# 28pins_schematic.net
KiCad netlist of a schematic drawn in Altium Designer
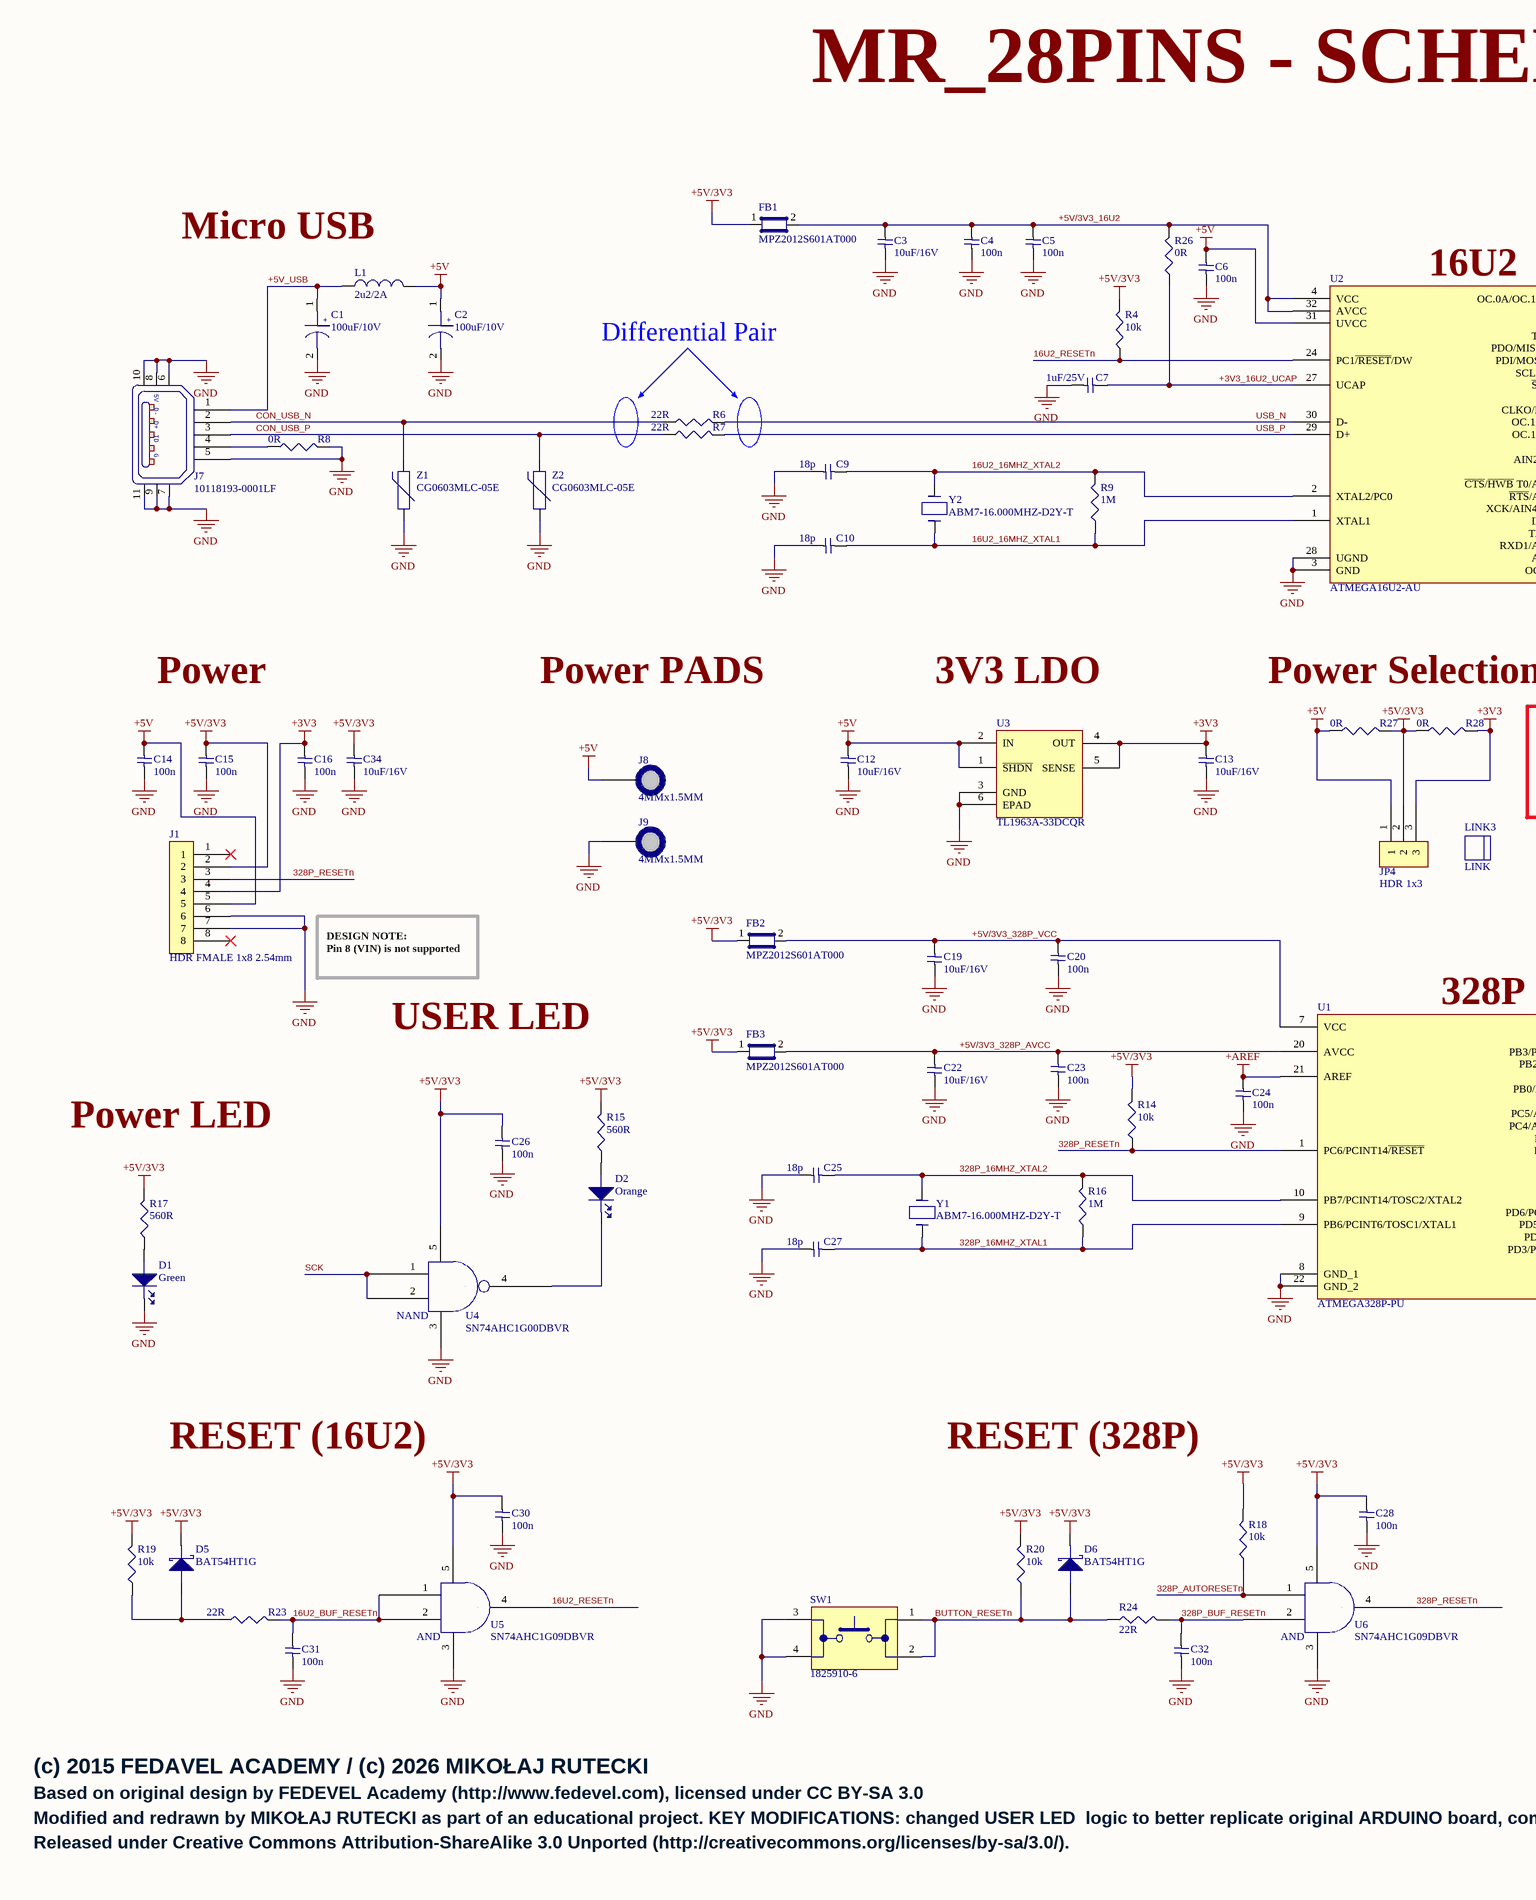
[diagram p0: 28pins_schematic.SchDoc, left]
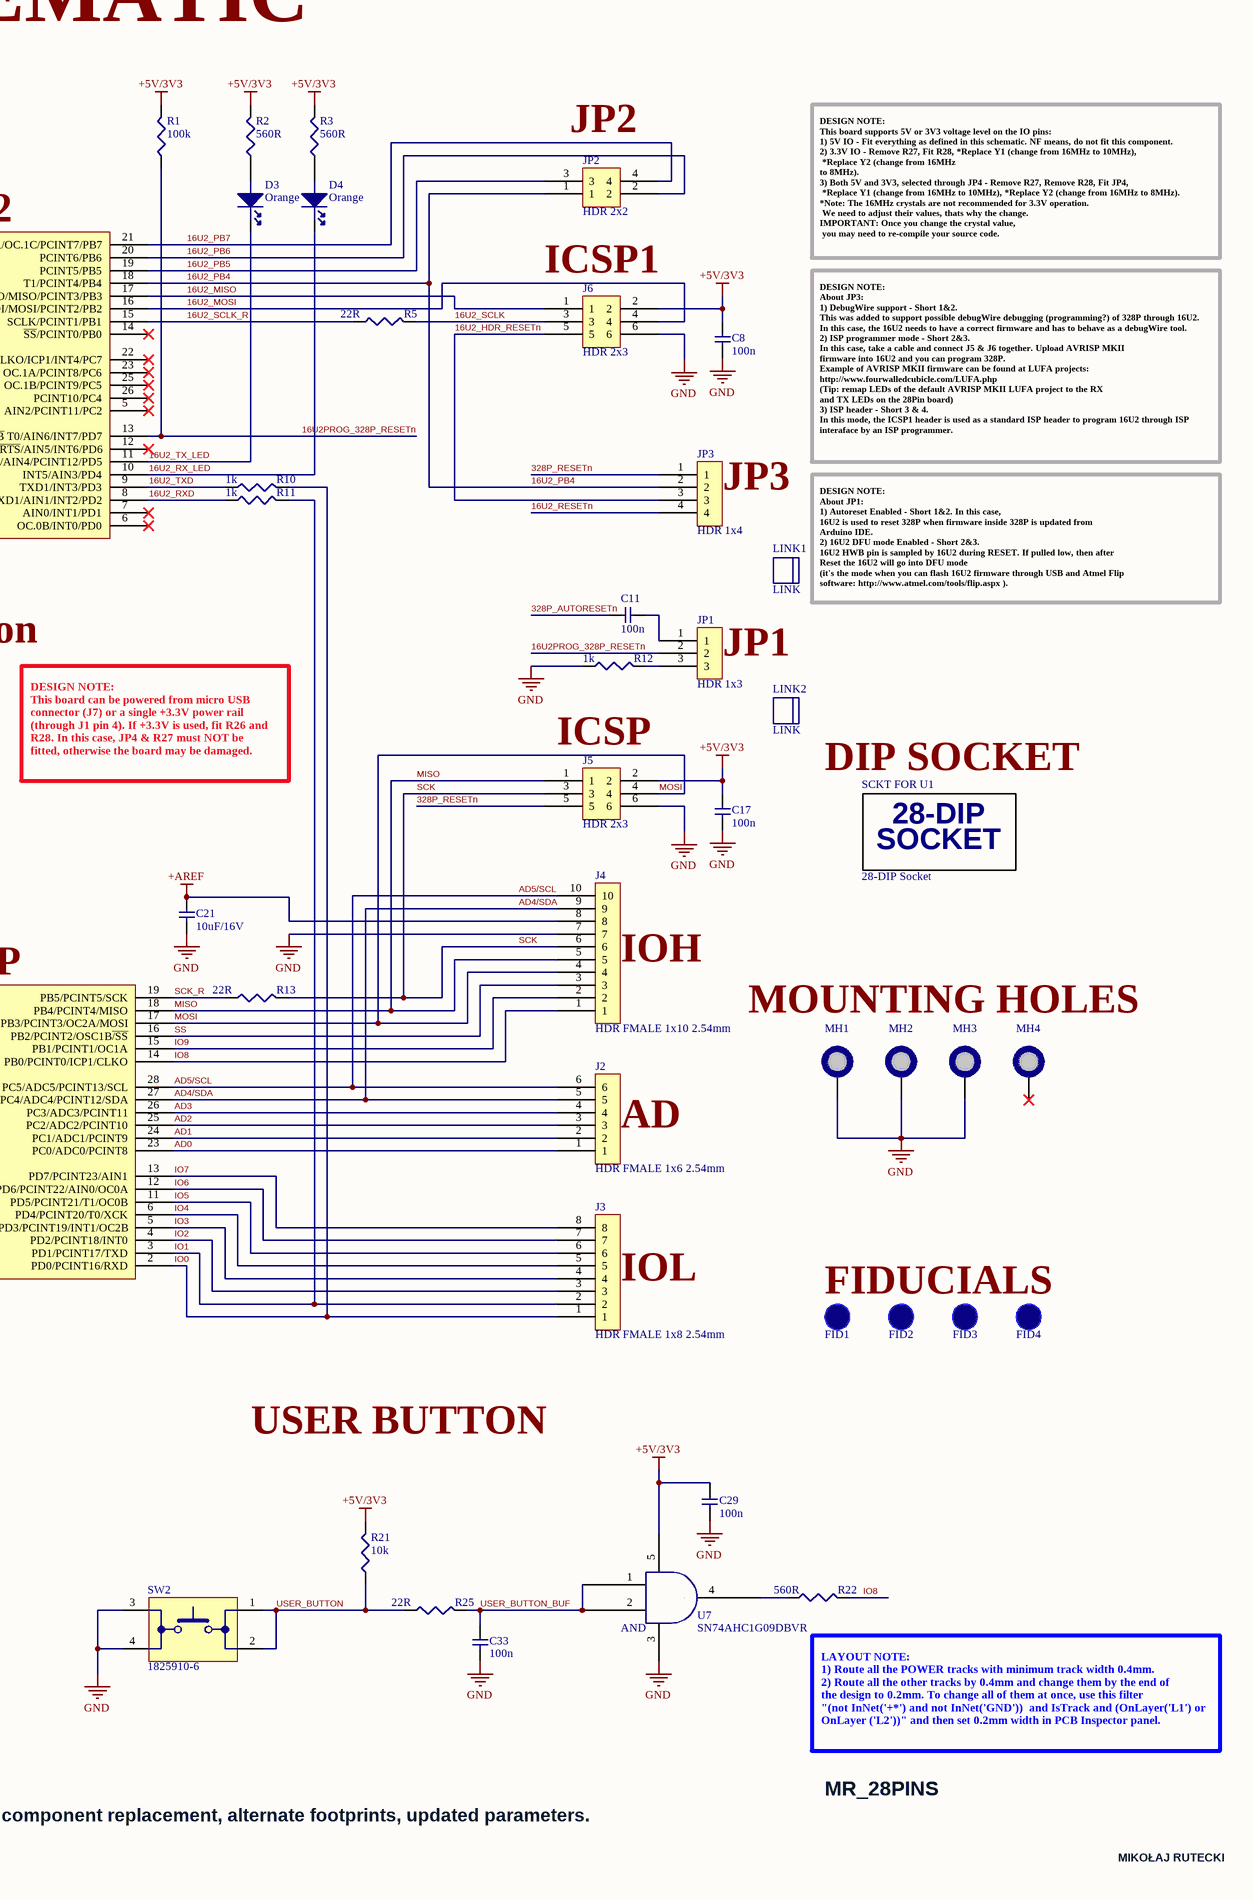
[diagram p1: 28pins_schematic.SchDoc, right]

(export (version "E")
  (design (tool "Eeschema 10.0.6"))
  (components
    (comp (ref "C1")
      (value "100uF/10V")
      (footprint "C_ALU_C_SIZE")
      (description "CAP ALUM 100UF 20% 10V SMD")
      (libsource (lib "28Pins_Project_V1I1") (part "EEE-1AA101WR"))
    )
    (comp (ref "C2")
      (value "100uF/10V")
      (footprint "C_ALU_C_SIZE")
      (description "CAP ALUM 100UF 20% 10V SMD")
      (libsource (lib "28Pins_Project_V1I1") (part "EEE-1AA101WR"))
    )
    (comp (ref "C3")
      (value "10uF/16V")
      (footprint "C0805")
      (description "CAP CER 10UF 16V X5R 0805")
      (libsource (lib "28Pins_Project_V1I1") (part "CGA4J1X5R1C106M125AC"))
    )
    (comp (ref "C4")
      (value "100n")
      (footprint "C0805")
      (description "CAP CER 0.1UF 50V X7R 0805")
      (libsource (lib "28Pins_Project_V1I1") (part "C2012X7R1H104K085AA"))
    )
    (comp (ref "C5")
      (value "100n")
      (footprint "C0805")
      (description "CAP CER 0.1UF 50V X7R 0805")
      (libsource (lib "28Pins_Project_V1I1") (part "C2012X7R1H104K085AA"))
    )
    (comp (ref "C6")
      (value "100n")
      (footprint "C0805")
      (description "CAP CER 0.1UF 50V X7R 0805")
      (libsource (lib "28Pins_Project_V1I1") (part "C2012X7R1H104K085AA"))
    )
    (comp (ref "C7")
      (value "1uF/25V")
      (footprint "C0805")
      (description "CAP CER 1UF 25V X5R 0805")
      (libsource (lib "28Pins_Project_V1I1") (part "C2012X5R1E105K125AA"))
    )
    (comp (ref "C8")
      (value "100n")
      (footprint "C0805")
      (description "CAP CER 0.1UF 50V X7R 0805")
      (libsource (lib "28Pins_Project_V1I1") (part "C2012X7R1H104K085AA"))
    )
    (comp (ref "C9")
      (value "18p")
      (footprint "C0805")
      (description "CAP CER 18PF 50V NP0 0805")
      (libsource (lib "28Pins_Project_V1I1") (part "C0805C180J5GACTU"))
    )
    (comp (ref "C10")
      (value "18p")
      (footprint "C0805")
      (description "CAP CER 18PF 50V NP0 0805")
      (libsource (lib "28Pins_Project_V1I1") (part "C0805C180J5GACTU"))
    )
    (comp (ref "C11")
      (value "100n")
      (footprint "C0805")
      (description "CAP CER 0.1UF 50V X7R 0805")
      (libsource (lib "28Pins_Project_V1I1") (part "C2012X7R1H104K085AA"))
    )
    (comp (ref "C12")
      (value "10uF/16V")
      (footprint "C0805")
      (description "CAP CER 10UF 16V X5R 0805")
      (libsource (lib "28Pins_Project_V1I1") (part "CGA4J1X5R1C106M125AC"))
    )
    (comp (ref "C13")
      (value "10uF/16V")
      (footprint "C0805")
      (description "CAP CER 10UF 16V X5R 0805")
      (libsource (lib "28Pins_Project_V1I1") (part "CGA4J1X5R1C106M125AC"))
    )
    (comp (ref "C14")
      (value "100n")
      (footprint "C0805")
      (description "CAP CER 0.1UF 50V X7R 0805")
      (libsource (lib "28Pins_Project_V1I1") (part "C2012X7R1H104K085AA"))
    )
    (comp (ref "C15")
      (value "100n")
      (footprint "C0805")
      (description "CAP CER 0.1UF 50V X7R 0805")
      (libsource (lib "28Pins_Project_V1I1") (part "C2012X7R1H104K085AA"))
    )
    (comp (ref "C16")
      (value "100n")
      (footprint "C0805")
      (description "CAP CER 0.1UF 50V X7R 0805")
      (libsource (lib "28Pins_Project_V1I1") (part "C2012X7R1H104K085AA"))
    )
    (comp (ref "C17")
      (value "100n")
      (footprint "C0805")
      (description "CAP CER 0.1UF 50V X7R 0805")
      (libsource (lib "28Pins_Project_V1I1") (part "C2012X7R1H104K085AA"))
    )
    (comp (ref "C19")
      (value "10uF/16V")
      (footprint "C0805")
      (description "CAP CER 10UF 16V X5R 0805")
      (libsource (lib "28Pins_Project_V1I1") (part "CGA4J1X5R1C106M125AC"))
    )
    (comp (ref "C20")
      (value "100n")
      (footprint "C0805")
      (description "CAP CER 0.1UF 50V X7R 0805")
      (libsource (lib "28Pins_Project_V1I1") (part "C2012X7R1H104K085AA"))
    )
    (comp (ref "C21")
      (value "10uF/16V")
      (footprint "C0805")
      (description "CAP CER 10UF 16V X5R 0805")
      (libsource (lib "28Pins_Project_V1I1") (part "CGA4J1X5R1C106M125AC"))
    )
    (comp (ref "C22")
      (value "10uF/16V")
      (footprint "C0805")
      (description "CAP CER 10UF 16V X5R 0805")
      (libsource (lib "28Pins_Project_V1I1") (part "CGA4J1X5R1C106M125AC"))
    )
    (comp (ref "C23")
      (value "100n")
      (footprint "C0805")
      (description "CAP CER 0.1UF 50V X7R 0805")
      (libsource (lib "28Pins_Project_V1I1") (part "C2012X7R1H104K085AA"))
    )
    (comp (ref "C24")
      (value "100n")
      (footprint "C0805")
      (description "CAP CER 0.1UF 50V X7R 0805")
      (libsource (lib "28Pins_Project_V1I1") (part "C2012X7R1H104K085AA"))
    )
    (comp (ref "C25")
      (value "18p")
      (footprint "C0805")
      (description "CAP CER 18PF 50V NP0 0805")
      (libsource (lib "28Pins_Project_V1I1") (part "C0805C180J5GACTU"))
    )
    (comp (ref "C26")
      (value "100n")
      (footprint "C0805")
      (description "CAP CER 0.1UF 50V X7R 0805")
      (libsource (lib "28Pins_Project_V1I1") (part "C2012X7R1H104K085AA"))
    )
    (comp (ref "C27")
      (value "18p")
      (footprint "C0805")
      (description "CAP CER 18PF 50V NP0 0805")
      (libsource (lib "28Pins_Project_V1I1") (part "C0805C180J5GACTU"))
    )
    (comp (ref "C28")
      (value "100n")
      (footprint "C0805")
      (description "CAP CER 0.1UF 50V X7R 0805")
      (libsource (lib "28Pins_Project_V1I1") (part "C2012X7R1H104K085AA"))
    )
    (comp (ref "C29")
      (value "100n")
      (footprint "C0805")
      (description "CAP CER 0.1UF 50V X7R 0805")
      (libsource (lib "28Pins_Project_V1I1") (part "C2012X7R1H104K085AA"))
    )
    (comp (ref "C30")
      (value "100n")
      (footprint "C0805")
      (description "CAP CER 0.1UF 50V X7R 0805")
      (libsource (lib "28Pins_Project_V1I1") (part "C2012X7R1H104K085AA"))
    )
    (comp (ref "C31")
      (value "100n")
      (footprint "C0805")
      (description "CAP CER 0.1UF 50V X7R 0805")
      (libsource (lib "28Pins_Project_V1I1") (part "C2012X7R1H104K085AA"))
    )
    (comp (ref "C32")
      (value "100n")
      (footprint "C0805")
      (description "CAP CER 0.1UF 50V X7R 0805")
      (libsource (lib "28Pins_Project_V1I1") (part "C2012X7R1H104K085AA"))
    )
    (comp (ref "C33")
      (value "100n")
      (footprint "C0805")
      (description "CAP CER 0.1UF 50V X7R 0805")
      (libsource (lib "28Pins_Project_V1I1") (part "C2012X7R1H104K085AA"))
    )
    (comp (ref "C34")
      (value "10uF/16V")
      (footprint "C0805")
      (description "CAP CER 10UF 16V X5R 0805")
      (libsource (lib "28Pins_Project_V1I1") (part "CGA4J1X5R1C106M125AC"))
    )
    (comp (ref "D1")
      (value "Green")
      (footprint "LED_0603")
      (description "LED GREEN DIFFUSED 0603 SMD")
      (libsource (lib "28Pins_Project_V1I1") (part "LG L29K-G2J1-24-0-2-R18-Z"))
    )
    (comp (ref "D2")
      (value "Orange")
      (footprint "LED_0603")
      (description "LED ORANGE DIFFUSED 0603 SMD")
      (libsource (lib "28Pins_Project_V1I1") (part "LO L29K-H2K1-24-0-2-R18-Z"))
    )
    (comp (ref "D3")
      (value "Orange")
      (footprint "LED_0603")
      (description "LED ORANGE DIFFUSED 0603 SMD")
      (libsource (lib "28Pins_Project_V1I1") (part "LO L29K-H2K1-24-0-2-R18-Z"))
    )
    (comp (ref "D4")
      (value "Orange")
      (footprint "LED_0603")
      (description "LED ORANGE DIFFUSED 0603 SMD")
      (libsource (lib "28Pins_Project_V1I1") (part "LO L29K-H2K1-24-0-2-R18-Z"))
    )
    (comp (ref "D5")
      (value "BAT54HT1G")
      (footprint "SOD323")
      (description "DIODE SCHOTTKY 30V 200MA SOD323")
      (libsource (lib "28Pins_Project_V1I1") (part "BAT54HT1GOSCT-ND"))
    )
    (comp (ref "D6")
      (value "BAT54HT1G")
      (footprint "SOD323")
      (description "DIODE SCHOTTKY 30V 200MA SOD323")
      (libsource (lib "28Pins_Project_V1I1") (part "BAT54HT1GOSCT-ND"))
    )
    (comp (ref "FB1")
      (value "MPZ2012S601AT000")
      (footprint "C0805")
      (description "FERRITE CHIP BEAD 600 OHM SMD")
      (libsource (lib "28Pins_Project_V1I1") (part "MPZ2012S601AT000"))
    )
    (comp (ref "FB2")
      (value "MPZ2012S601AT000")
      (footprint "C0805")
      (description "FERRITE CHIP BEAD 600 OHM SMD")
      (libsource (lib "28Pins_Project_V1I1") (part "MPZ2012S601AT000"))
    )
    (comp (ref "FB3")
      (value "MPZ2012S601AT000")
      (footprint "C0805")
      (description "FERRITE CHIP BEAD 600 OHM SMD")
      (libsource (lib "28Pins_Project_V1I1") (part "MPZ2012S601AT000"))
    )
    (comp (ref "FID1")
      (value "FID_1MM")
      (footprint "FID_40x120D")
      (description "Fiducial 40mil Diameter, 120mil Mask")
      (libsource (lib "28Pins_Project_V1I1") (part "FID_1MM"))
    )
    (comp (ref "FID2")
      (value "FID_1MM")
      (footprint "FID_40x120D")
      (description "Fiducial 40mil Diameter, 120mil Mask")
      (libsource (lib "28Pins_Project_V1I1") (part "FID_1MM"))
    )
    (comp (ref "FID3")
      (value "FID_1MM")
      (footprint "FID_40x120D")
      (description "Fiducial 40mil Diameter, 120mil Mask")
      (libsource (lib "28Pins_Project_V1I1") (part "FID_1MM"))
    )
    (comp (ref "FID4")
      (value "FID_1MM")
      (footprint "FID_40x120D")
      (description "Fiducial 40mil Diameter, 120mil Mask")
      (libsource (lib "28Pins_Project_V1I1") (part "FID_1MM"))
    )
    (comp (ref "J1")
      (value "HDR FMALE 1x8 2.54mm")
      (footprint "HDR_Female_1x8_2.54mm - duplicate")
      (description "8-WAY SIL VERT SOCKET L/FREE")
      (libsource (lib "") (part "M20-7820842_1"))
    )
    (comp (ref "J2")
      (value "HDR FMALE 1x6 2.54mm")
      (footprint "HDR_Female_1x6_2.54mm")
      (description "6-WAY SIL VERT SOCKET L/FREE")
      (libsource (lib "28Pins_Project_V1I1") (part "M20-7820646"))
    )
    (comp (ref "J3")
      (value "HDR FMALE 1x8 2.54mm")
      (footprint "HDR_Female_1x8_2.54mm - duplicate")
      (description "8-WAY SIL VERT SOCKET L/FREE")
      (libsource (lib "28Pins_Project_V1I1") (part "M20-7820842"))
    )
    (comp (ref "J4")
      (value "HDR FMALE 1x10 2.54mm")
      (footprint "HDR_Female_1x10_2.54mm")
      (description "10-WAY SIL VERT SOCKET L/FREE")
      (libsource (lib "28Pins_Project_V1I1") (part "M20-7821046"))
    )
    (comp (ref "J5")
      (value "HDR 2x3")
      (footprint "HDR_2x3_2.54MM")
      (description "CONN HEADER VERT 6POS 2.54MM")
      (libsource (lib "28Pins_Project_V1I1") (part "87227-3"))
    )
    (comp (ref "J6")
      (value "HDR 2x3")
      (footprint "HDR_2x3_2.54MM")
      (description "CONN HEADER VERT 6POS 2.54MM")
      (libsource (lib "28Pins_Project_V1I1") (part "87227-3"))
    )
    (comp (ref "J7")
      (value "10118193-0001LF")
      (footprint "10118193")
      (description "CONN RCPT USB2.0 MICRO B SMD R/A")
      (libsource (lib "28Pins_Project_V1I1") (part "10118193-0001LF"))
    )
    (comp (ref "J8")
      (value "4MMx1.5MM")
      (footprint "PAD_WITH_HOLE_4MMx1.5MM")
      (description "Pad with a hole 4mmx1.5mm")
      (libsource (lib "28Pins_Project_V1I1") (part "PAD_WITH_HOLE_4MMx1.5MM"))
    )
    (comp (ref "J9")
      (value "4MMx1.5MM")
      (footprint "PAD_WITH_HOLE_4MMx1.5MM")
      (description "Pad with a hole 4mmx1.5mm")
      (libsource (lib "28Pins_Project_V1I1") (part "PAD_WITH_HOLE_4MMx1.5MM"))
    )
    (comp (ref "JP1")
      (value "HDR 1x3")
      (footprint "HDR_1x3_2.54mm")
      (description "CONN HEADER VERT 3POS 2.54MM")
      (libsource (lib "28Pins_Project_V1I1") (part "68000-103HLF"))
    )
    (comp (ref "JP2")
      (value "HDR 2x2")
      (footprint "HDR_2x2_2.54mm")
      (description "CONN HEADER VERT 4POS 2.54MM")
      (libsource (lib "28Pins_Project_V1I1") (part "5-146256-2"))
    )
    (comp (ref "JP3")
      (value "HDR 1x4")
      (footprint "HDR_1x4_2.54mm")
      (description "CONN HEADER VERT 4POS 2.54MM")
      (libsource (lib "28Pins_Project_V1I1") (part "68001-204HLF"))
    )
    (comp (ref "JP4")
      (value "HDR 1x3")
      (footprint "HDR_1x3_2.54mm")
      (description "CONN HEADER VERT 3POS 2.54MM")
      (libsource (lib "") (part "68000-103HLF_1"))
    )
    (comp (ref "L1")
      (value "2u2/2A")
      (footprint "C1210_IND")
      (description "FIXED IND 2.2UH 2A 80 MOHM SMD")
      (libsource (lib "28Pins_Project_V1I1") (part "L1210R2R2MDWIT"))
    )
    (comp (ref "LINK1")
      (value "LINK")
      (description "CONN JUMPER SHORTING .100\" GOLD")
      (libsource (lib "28Pins_Project_V1I1") (part "QPC02SXGN-RC"))
    )
    (comp (ref "LINK2")
      (value "LINK")
      (description "CONN JUMPER SHORTING .100\" GOLD")
      (libsource (lib "28Pins_Project_V1I1") (part "QPC02SXGN-RC"))
    )
    (comp (ref "LINK3")
      (value "LINK")
      (description "CONN JUMPER SHORTING .100\" GOLD")
      (libsource (lib "28Pins_Project_V1I1") (part "QPC02SXGN-RC"))
    )
    (comp (ref "MH1")
      (value "MH_7.4MMC_3.2MMD")
      (footprint "MH_7.4MMD_3.2MMD")
      (description "Mounting Hole 7.4mm Diameter, 3.2mm Drill")
      (libsource (lib "28Pins_Project_V1I1") (part "MH_7.4MMC_3.2MMD"))
    )
    (comp (ref "MH2")
      (value "MH_7.4MMC_3.2MMD")
      (footprint "MH_7.4MMD_3.2MMD")
      (description "Mounting Hole 7.4mm Diameter, 3.2mm Drill")
      (libsource (lib "28Pins_Project_V1I1") (part "MH_7.4MMC_3.2MMD"))
    )
    (comp (ref "MH3")
      (value "MH_7.4MMC_3.2MMD")
      (footprint "MH_7.4MMD_3.2MMD")
      (description "Mounting Hole 7.4mm Diameter, 3.2mm Drill")
      (libsource (lib "28Pins_Project_V1I1") (part "MH_7.4MMC_3.2MMD"))
    )
    (comp (ref "MH4")
      (value "MH_7.4MMNC_3.2MMD")
      (footprint "MH_7.4MMD_3.2MMD_NON_COPPER_NPTH")
      (description "Hole 7.4mm Diameter (NON COPPER), 3.2mm Drill NPTH")
      (libsource (lib "28Pins_Project_V1I1") (part "MH_7.4MMNC_3.2MMD"))
    )
    (comp (ref "R1")
      (value "100k")
      (footprint "R0805")
      (description "RES 100K OHM 5% 1/8W 0805")
      (libsource (lib "28Pins_Project_V1I1") (part "RC0805JR-07100KL"))
    )
    (comp (ref "R2")
      (value "560R")
      (footprint "R0805")
      (description "RES 560 OHM 1% 1/8W 0805")
      (libsource (lib "28Pins_Project_V1I1") (part "RC0805FR-07560RL"))
    )
    (comp (ref "R3")
      (value "560R")
      (footprint "R0805")
      (description "RES 560 OHM 1% 1/8W 0805")
      (libsource (lib "28Pins_Project_V1I1") (part "RC0805FR-07560RL"))
    )
    (comp (ref "R4")
      (value "10k")
      (footprint "R0805")
      (description "RES 10K OHM 1% 1/8W 0805")
      (libsource (lib "28Pins_Project_V1I1") (part "RC0805FR-0710KL"))
    )
    (comp (ref "R5")
      (value "22R")
      (footprint "R0805")
      (description "RES SMD 22 OHM 1% 1/8W 0805")
      (libsource (lib "28Pins_Project_V1I1") (part "RT0805FRE0722RL"))
    )
    (comp (ref "R6")
      (value "22R")
      (footprint "R0805")
      (description "RES SMD 22 OHM 1% 1/8W 0805")
      (libsource (lib "28Pins_Project_V1I1") (part "RT0805FRE0722RL"))
    )
    (comp (ref "R7")
      (value "22R")
      (footprint "R0805")
      (description "RES SMD 22 OHM 1% 1/8W 0805")
      (libsource (lib "28Pins_Project_V1I1") (part "RT0805FRE0722RL"))
    )
    (comp (ref "R8")
      (value "0R")
      (footprint "R0805")
      (description "RES 0 OHM JUMPER 1/8W 0805")
      (libsource (lib "28Pins_Project_V1I1") (part "RC0805JR-070RL"))
    )
    (comp (ref "R9")
      (value "1M")
      (footprint "R0805")
      (description "RES SMD 1M OHM 1% 1/8W 0805")
      (libsource (lib "28Pins_Project_V1I1") (part "RC0805FR-071ML"))
    )
    (comp (ref "R10")
      (value "1k")
      (footprint "R0805")
      (description "RES 1K OHM 1% 1/8W 0805")
      (libsource (lib "28Pins_Project_V1I1") (part "RC0805FR-071KL"))
    )
    (comp (ref "R11")
      (value "1k")
      (footprint "R0805")
      (description "RES 1K OHM 1% 1/8W 0805")
      (libsource (lib "28Pins_Project_V1I1") (part "RC0805FR-071KL"))
    )
    (comp (ref "R12")
      (value "1k")
      (footprint "R0805")
      (description "RES 1K OHM 1% 1/8W 0805")
      (libsource (lib "28Pins_Project_V1I1") (part "RC0805FR-071KL"))
    )
    (comp (ref "R13")
      (value "22R")
      (footprint "R0805")
      (description "RES SMD 22 OHM 1% 1/8W 0805")
      (libsource (lib "28Pins_Project_V1I1") (part "RT0805FRE0722RL"))
    )
    (comp (ref "R14")
      (value "10k")
      (footprint "R0805")
      (description "RES 10K OHM 1% 1/8W 0805")
      (libsource (lib "28Pins_Project_V1I1") (part "RC0805FR-0710KL"))
    )
    (comp (ref "R15")
      (value "560R")
      (footprint "R0805")
      (description "RES 560 OHM 1% 1/8W 0805")
      (libsource (lib "28Pins_Project_V1I1") (part "RC0805FR-07560RL"))
    )
    (comp (ref "R16")
      (value "1M")
      (footprint "R0805")
      (description "RES SMD 1M OHM 1% 1/8W 0805")
      (libsource (lib "28Pins_Project_V1I1") (part "RC0805FR-071ML"))
    )
    (comp (ref "R17")
      (value "560R")
      (footprint "R0805")
      (description "RES 560 OHM 1% 1/8W 0805")
      (libsource (lib "28Pins_Project_V1I1") (part "RC0805FR-07560RL"))
    )
    (comp (ref "R18")
      (value "10k")
      (footprint "R0805")
      (description "RES 10K OHM 1% 1/8W 0805")
      (libsource (lib "28Pins_Project_V1I1") (part "RC0805FR-0710KL"))
    )
    (comp (ref "R19")
      (value "10k")
      (footprint "R0805")
      (description "RES 10K OHM 1% 1/8W 0805")
      (libsource (lib "28Pins_Project_V1I1") (part "RC0805FR-0710KL"))
    )
    (comp (ref "R20")
      (value "10k")
      (footprint "R0805")
      (description "RES 10K OHM 1% 1/8W 0805")
      (libsource (lib "28Pins_Project_V1I1") (part "RC0805FR-0710KL"))
    )
    (comp (ref "R21")
      (value "10k")
      (footprint "R0805")
      (description "RES 10K OHM 1% 1/8W 0805")
      (libsource (lib "28Pins_Project_V1I1") (part "RC0805FR-0710KL"))
    )
    (comp (ref "R22")
      (value "560R")
      (footprint "R0805")
      (description "RES 560 OHM 1% 1/8W 0805")
      (libsource (lib "28Pins_Project_V1I1") (part "RC0805FR-07560RL"))
    )
    (comp (ref "R23")
      (value "22R")
      (footprint "R0805")
      (description "RES SMD 22 OHM 1% 1/8W 0805")
      (libsource (lib "28Pins_Project_V1I1") (part "RT0805FRE0722RL"))
    )
    (comp (ref "R24")
      (value "22R")
      (footprint "R0805")
      (description "RES SMD 22 OHM 1% 1/8W 0805")
      (libsource (lib "28Pins_Project_V1I1") (part "RT0805FRE0722RL"))
    )
    (comp (ref "R25")
      (value "22R")
      (footprint "R0805")
      (description "RES SMD 22 OHM 1% 1/8W 0805")
      (libsource (lib "28Pins_Project_V1I1") (part "RT0805FRE0722RL"))
    )
    (comp (ref "R26")
      (value "0R")
      (footprint "R0805")
      (description "RES 0 OHM JUMPER 1/8W 0805")
      (libsource (lib "28Pins_Project_V1I1") (part "RC0805JR-070RL"))
    )
    (comp (ref "R27")
      (value "0R")
      (footprint "R0805")
      (description "RES 0 OHM JUMPER 1/8W 0805")
      (libsource (lib "28Pins_Project_V1I1") (part "RC0805JR-070RL"))
    )
    (comp (ref "R28")
      (value "0R")
      (footprint "R0805")
      (description "RES 0 OHM JUMPER 1/8W 0805")
      (libsource (lib "28Pins_Project_V1I1") (part "RC0805JR-070RL"))
    )
    (comp (ref "SCKT FOR U1")
      (value "28-DIP Socket")
      (footprint "28-DIP_7.62mm_SOCKET")
      (description "CONN IC DIP SOCKET 28POS TIN")
      (libsource (lib "28Pins_Project_V1I1") (part "4828-3004-CP"))
    )
    (comp (ref "SW1")
      (value "1825910-6")
      (footprint "1825910-6")
      (description "SWITCH TACTILE SPST-NO 0.05A 24V")
      (libsource (lib "28Pins_Project_V1I1") (part "1825910-6"))
    )
    (comp (ref "SW2")
      (value "1825910-6")
      (footprint "1825910-6")
      (description "SWITCH TACTILE SPST-NO 0.05A 24V")
      (libsource (lib "28Pins_Project_V1I1") (part "1825910-6"))
    )
    (comp (ref "U1")
      (value "ATMEGA328P-PU")
      (footprint "28_DIP_7.62mm")
      (description "IC MCU 8BIT 32KB FLASH 28DIP")
      (libsource (lib "28Pins_Project_V1I1") (part "ATMEGA328P-PU"))
    )
    (comp (ref "U2")
      (value "ATMEGA16U2-AU")
      (footprint "TQFP32")
      (description "IC MCU 8BIT 16KB FLASH 32TQFP")
      (libsource (lib "28Pins_Project_V1I1") (part "ATMEGA16U2-AU"))
    )
    (comp (ref "U3")
      (value "TL1963A-33DCQR")
      (footprint "DCQ(R-PDSO-G6)")
      (description "IC REG LIN 3.3V 1.5A SOT-223-6")
      (libsource (lib "28Pins_Project_V1I1") (part "TL1963A-33DCQR"))
    )
    (comp (ref "U4")
      (value "SN74AHC1G00DBVR")
      (footprint "DBV_DOT_23_5")
      (description "IC GATE NAND 1CH 2-INP SOT23-5")
      (libsource (lib "28Pins_Project_V1I1") (part "SN74AHC1G00DBVR"))
    )
    (comp (ref "U5")
      (value "SN74AHC1G09DBVR")
      (footprint "DBV_DOT_23_5")
      (description "IC GATE AND 1CH 2-INP SOT23-5")
      (libsource (lib "28Pins_Project_V1I1") (part "SN74AHC1G09DBVR"))
    )
    (comp (ref "U6")
      (value "SN74AHC1G09DBVR")
      (footprint "DBV_DOT_23_5")
      (description "IC GATE AND 1CH 2-INP SOT23-5")
      (libsource (lib "28Pins_Project_V1I1") (part "SN74AHC1G09DBVR"))
    )
    (comp (ref "U7")
      (value "SN74AHC1G09DBVR")
      (footprint "DBV_DOT_23_5")
      (description "IC GATE AND 1CH 2-INP SOT23-5")
      (libsource (lib "28Pins_Project_V1I1") (part "SN74AHC1G09DBVR"))
    )
    (comp (ref "Y1")
      (value "ABM7-16.000MHZ-D2Y-T")
      (footprint "ABM7_v1_1_BIG")
      (description "CRYSTAL 16.0000MHZ 18PF SMD")
      (libsource (lib "28Pins_Project_V1I1") (part "ABM7-16.000MHZ-D2Y-T"))
    )
    (comp (ref "Y2")
      (value "ABM7-16.000MHZ-D2Y-T")
      (footprint "ABM7_v1_1_BIG")
      (description "CRYSTAL 16.0000MHZ 18PF SMD")
      (libsource (lib "28Pins_Project_V1I1") (part "ABM7-16.000MHZ-D2Y-T"))
    )
    (comp (ref "Z1")
      (value "CG0603MLC-05E")
      (footprint "R0603")
      (description "VARISTOR 0603")
      (libsource (lib "28Pins_Project_V1I1") (part "CG0603MLC-05E"))
    )
    (comp (ref "Z2")
      (value "CG0603MLC-05E")
      (footprint "R0603")
      (description "VARISTOR 0603")
      (libsource (lib "28Pins_Project_V1I1") (part "CG0603MLC-05E"))
    )
  )
  (nets
    (net (code "1") (name "+3V3") (class "Default")
      (node (ref "C13") (pin "2") (pinfunction "2_2") (pintype "passive"))
      (node (ref "C16") (pin "2") (pinfunction "2_2") (pintype "passive"))
      (node (ref "J1") (pin "4") (pinfunction "4_4") (pintype "passive"))
      (node (ref "JP4") (pin "3") (pinfunction "3_3") (pintype "passive"))
      (node (ref "R28") (pin "2") (pinfunction "2_2") (pintype "passive"))
      (node (ref "U3") (pin "4") (pinfunction "OUT_4") (pintype "passive"))
      (node (ref "U3") (pin "5") (pinfunction "SENSE_5") (pintype "passive"))
    )
    (net (code "2") (name "+5V") (class "Default")
      (node (ref "C12") (pin "2") (pinfunction "2_2") (pintype "passive"))
      (node (ref "C14") (pin "2") (pinfunction "2_2") (pintype "passive"))
      (node (ref "C2") (pin "1") (pinfunction "1_1") (pintype "passive"))
      (node (ref "C6") (pin "2") (pinfunction "2_2") (pintype "passive"))
      (node (ref "J1") (pin "5") (pinfunction "5_5") (pintype "passive"))
      (node (ref "J8") (pin "1") (pinfunction "1_1") (pintype "passive"))
      (node (ref "JP4") (pin "1") (pinfunction "1_1") (pintype "passive"))
      (node (ref "L1") (pin "2") (pinfunction "2_2") (pintype "passive"))
      (node (ref "R27") (pin "1") (pinfunction "1_1") (pintype "passive"))
      (node (ref "U2") (pin "31") (pinfunction "UVCC_31") (pintype "passive"))
      (node (ref "U3") (pin "1") (pinfunction "~{SHDN}_1") (pintype "passive"))
      (node (ref "U3") (pin "2") (pinfunction "IN_2") (pintype "passive"))
    )
    (net (code "3") (name "+5V{slash}3V3") (class "Default")
      (node (ref "C15") (pin "2") (pinfunction "2_2") (pintype "passive"))
      (node (ref "C17") (pin "2") (pinfunction "2_2") (pintype "passive"))
      (node (ref "C26") (pin "2") (pinfunction "2_2") (pintype "passive"))
      (node (ref "C28") (pin "2") (pinfunction "2_2") (pintype "passive"))
      (node (ref "C29") (pin "2") (pinfunction "2_2") (pintype "passive"))
      (node (ref "C30") (pin "2") (pinfunction "2_2") (pintype "passive"))
      (node (ref "C34") (pin "2") (pinfunction "2_2") (pintype "passive"))
      (node (ref "C8") (pin "2") (pinfunction "2_2") (pintype "passive"))
      (node (ref "D5") (pin "1") (pinfunction "Cathode_1") (pintype "passive"))
      (node (ref "D6") (pin "1") (pinfunction "Cathode_1") (pintype "passive"))
      (node (ref "FB1") (pin "1") (pinfunction "1_1") (pintype "passive"))
      (node (ref "FB2") (pin "1") (pinfunction "1_1") (pintype "passive"))
      (node (ref "FB3") (pin "1") (pinfunction "1_1") (pintype "passive"))
      (node (ref "J1") (pin "2") (pinfunction "2_2") (pintype "passive"))
      (node (ref "J5") (pin "2") (pinfunction "2_2") (pintype "passive"))
      (node (ref "J6") (pin "2") (pinfunction "2_2") (pintype "passive"))
      (node (ref "JP4") (pin "2") (pinfunction "2_2") (pintype "passive"))
      (node (ref "R1") (pin "2") (pinfunction "2_2") (pintype "passive"))
      (node (ref "R14") (pin "2") (pinfunction "2_2") (pintype "passive"))
      (node (ref "R15") (pin "2") (pinfunction "2_2") (pintype "passive"))
      (node (ref "R17") (pin "2") (pinfunction "2_2") (pintype "passive"))
      (node (ref "R18") (pin "2") (pinfunction "2_2") (pintype "passive"))
      (node (ref "R19") (pin "2") (pinfunction "2_2") (pintype "passive"))
      (node (ref "R2") (pin "2") (pinfunction "2_2") (pintype "passive"))
      (node (ref "R20") (pin "2") (pinfunction "2_2") (pintype "passive"))
      (node (ref "R21") (pin "2") (pinfunction "2_2") (pintype "passive"))
      (node (ref "R27") (pin "2") (pinfunction "2_2") (pintype "passive"))
      (node (ref "R28") (pin "1") (pinfunction "1_1") (pintype "passive"))
      (node (ref "R3") (pin "2") (pinfunction "2_2") (pintype "passive"))
      (node (ref "R4") (pin "2") (pinfunction "2_2") (pintype "passive"))
      (node (ref "U4") (pin "5") (pinfunction "5_5") (pintype "passive"))
      (node (ref "U5") (pin "5") (pinfunction "5_5") (pintype "passive"))
      (node (ref "U6") (pin "5") (pinfunction "5_5") (pintype "passive"))
      (node (ref "U7") (pin "5") (pinfunction "5_5") (pintype "passive"))
    )
    (net (code "4") (name "+AREF") (class "Default")
      (node (ref "C21") (pin "2") (pinfunction "2_2") (pintype "passive"))
      (node (ref "C24") (pin "2") (pinfunction "2_2") (pintype "passive"))
      (node (ref "J4") (pin "8") (pinfunction "8_8") (pintype "passive"))
      (node (ref "U1") (pin "21") (pinfunction "AREF_21") (pintype "passive"))
    )
    (net (code "5") (name "/+3V3_16U2_UCAP") (class "Default")
      (node (ref "C7") (pin "2") (pinfunction "2_2") (pintype "passive"))
      (node (ref "R26") (pin "1") (pinfunction "1_1") (pintype "passive"))
      (node (ref "U2") (pin "27") (pinfunction "UCAP_27") (pintype "passive"))
    )
    (net (code "6") (name "/+5V_USB") (class "Default")
      (node (ref "C1") (pin "1") (pinfunction "1_1") (pintype "passive"))
      (node (ref "J7") (pin "1") (pinfunction "1_1") (pintype "passive"))
      (node (ref "L1") (pin "1") (pinfunction "1_1") (pintype "passive"))
    )
    (net (code "7") (name "/+5V{slash}3V3_16U2") (class "Default")
      (node (ref "C3") (pin "2") (pinfunction "2_2") (pintype "passive"))
      (node (ref "C4") (pin "2") (pinfunction "2_2") (pintype "passive"))
      (node (ref "C5") (pin "2") (pinfunction "2_2") (pintype "passive"))
      (node (ref "FB1") (pin "2") (pinfunction "2_2") (pintype "passive"))
      (node (ref "R26") (pin "2") (pinfunction "2_2") (pintype "passive"))
      (node (ref "U2") (pin "32") (pinfunction "AVCC_32") (pintype "passive"))
      (node (ref "U2") (pin "4") (pinfunction "VCC_4") (pintype "passive"))
    )
    (net (code "8") (name "/+5V{slash}3V3_328P_AVCC") (class "Default")
      (node (ref "C22") (pin "1") (pinfunction "1_1") (pintype "passive"))
      (node (ref "C23") (pin "2") (pinfunction "2_2") (pintype "passive"))
      (node (ref "FB3") (pin "2") (pinfunction "2_2") (pintype "passive"))
      (node (ref "U1") (pin "20") (pinfunction "AVCC_20") (pintype "passive"))
    )
    (net (code "9") (name "/+5V{slash}3V3_328P_VCC") (class "Default")
      (node (ref "C19") (pin "1") (pinfunction "1_1") (pintype "passive"))
      (node (ref "C20") (pin "2") (pinfunction "2_2") (pintype "passive"))
      (node (ref "FB2") (pin "2") (pinfunction "2_2") (pintype "passive"))
      (node (ref "U1") (pin "7") (pinfunction "VCC_7") (pintype "passive"))
    )
    (net (code "10") (name "/16U2PROG_328P_RESETn") (class "Default")
      (node (ref "JP1") (pin "2") (pinfunction "2_2") (pintype "passive"))
      (node (ref "R1") (pin "1") (pinfunction "1_1") (pintype "passive"))
      (node (ref "U2") (pin "13") (pinfunction "~{CTS}/~{HWB}_T0/AIN6/INT7/PD7_13") (pintype "passive"))
    )
    (net (code "11") (name "/16U2_16MHZ_XTAL1") (class "Default")
      (node (ref "C10") (pin "1") (pinfunction "1_1") (pintype "passive"))
      (node (ref "R9") (pin "1") (pinfunction "1_1") (pintype "passive"))
      (node (ref "U2") (pin "1") (pinfunction "XTAL1_1") (pintype "passive"))
      (node (ref "Y2") (pin "1") (pinfunction "1_1") (pintype "passive"))
    )
    (net (code "12") (name "/16U2_16MHZ_XTAL2") (class "Default")
      (node (ref "C9") (pin "1") (pinfunction "1_1") (pintype "passive"))
      (node (ref "R9") (pin "2") (pinfunction "2_2") (pintype "passive"))
      (node (ref "U2") (pin "2") (pinfunction "XTAL2/PC0_2") (pintype "passive"))
      (node (ref "Y2") (pin "2") (pinfunction "2_2") (pintype "passive"))
    )
    (net (code "13") (name "/16U2_BUF_RESETn") (class "Default")
      (node (ref "C31") (pin "2") (pinfunction "2_2") (pintype "passive"))
      (node (ref "R23") (pin "2") (pinfunction "2_2") (pintype "passive"))
      (node (ref "U5") (pin "1") (pinfunction "1_1") (pintype "passive"))
      (node (ref "U5") (pin "2") (pinfunction "2_2") (pintype "passive"))
    )
    (net (code "14") (name "/16U2_HDR_RESETn") (class "Default")
      (node (ref "J6") (pin "5") (pinfunction "5_5") (pintype "passive"))
      (node (ref "JP3") (pin "3") (pinfunction "3_3") (pintype "passive"))
    )
    (net (code "15") (name "/16U2_MISO") (class "Default")
      (node (ref "J6") (pin "1") (pinfunction "1_1") (pintype "passive"))
      (node (ref "U2") (pin "17") (pinfunction "PDO/MISO/PCINT3/PB3_17") (pintype "passive"))
    )
    (net (code "16") (name "/16U2_MOSI") (class "Default")
      (node (ref "J6") (pin "4") (pinfunction "4_4") (pintype "passive"))
      (node (ref "U2") (pin "16") (pinfunction "PDI/MOSI/PCINT2/PB2_16") (pintype "passive"))
    )
    (net (code "17") (name "/16U2_PB4") (class "Default")
      (node (ref "JP2") (pin "1") (pinfunction "1_1") (pintype "passive"))
      (node (ref "JP3") (pin "2") (pinfunction "2_2") (pintype "passive"))
      (node (ref "U2") (pin "18") (pinfunction "T1/PCINT4/PB4_18") (pintype "passive"))
    )
    (net (code "18") (name "/16U2_PB5") (class "Default")
      (node (ref "JP2") (pin "3") (pinfunction "3_3") (pintype "passive"))
      (node (ref "U2") (pin "19") (pinfunction "PCINT5/PB5_19") (pintype "passive"))
    )
    (net (code "19") (name "/16U2_PB6") (class "Default")
      (node (ref "JP2") (pin "2") (pinfunction "2_2") (pintype "passive"))
      (node (ref "U2") (pin "20") (pinfunction "PCINT6/PB6_20") (pintype "passive"))
    )
    (net (code "20") (name "/16U2_PB7") (class "Default")
      (node (ref "JP2") (pin "4") (pinfunction "4_4") (pintype "passive"))
      (node (ref "U2") (pin "21") (pinfunction "OC.0A/OC.1C/PCINT7/PB7_21") (pintype "passive"))
    )
    (net (code "21") (name "/16U2_RESETn") (class "Default")
      (node (ref "JP3") (pin "4") (pinfunction "4_4") (pintype "passive"))
      (node (ref "R4") (pin "1") (pinfunction "1_1") (pintype "passive"))
      (node (ref "U2") (pin "24") (pinfunction "PC1~{/RESET}/DW_24") (pintype "passive"))
      (node (ref "U5") (pin "4") (pinfunction "4_4") (pintype "passive"))
    )
    (net (code "22") (name "/16U2_RXD") (class "Default")
      (node (ref "R11") (pin "1") (pinfunction "1_1") (pintype "passive"))
      (node (ref "U2") (pin "8") (pinfunction "RXD1/AIN1/INT2/PD2_8") (pintype "passive"))
    )
    (net (code "23") (name "/16U2_RX_LED") (class "Default")
      (node (ref "D4") (pin "1") (pinfunction "Cathode_1") (pintype "passive"))
      (node (ref "U2") (pin "10") (pinfunction "INT5/AIN3/PD4_10") (pintype "passive"))
    )
    (net (code "24") (name "/16U2_SCLK") (class "Default")
      (node (ref "J6") (pin "3") (pinfunction "3_3") (pintype "passive"))
      (node (ref "R5") (pin "2") (pinfunction "2_2") (pintype "passive"))
    )
    (net (code "25") (name "/16U2_SCLK_R") (class "Default")
      (node (ref "R5") (pin "1") (pinfunction "1_1") (pintype "passive"))
      (node (ref "U2") (pin "15") (pinfunction "SCLK/PCINT1/PB1_15") (pintype "passive"))
    )
    (net (code "26") (name "/16U2_TXD") (class "Default")
      (node (ref "R10") (pin "1") (pinfunction "1_1") (pintype "passive"))
      (node (ref "U2") (pin "9") (pinfunction "TXD1/INT3/PD3_9") (pintype "passive"))
    )
    (net (code "27") (name "/16U2_TX_LED") (class "Default")
      (node (ref "D3") (pin "1") (pinfunction "Cathode_1") (pintype "passive"))
      (node (ref "U2") (pin "11") (pinfunction "XCK/AIN4/PCINT12/PD5_11") (pintype "passive"))
    )
    (net (code "28") (name "/328P_16MHZ_XTAL1") (class "Default")
      (node (ref "C27") (pin "1") (pinfunction "1_1") (pintype "passive"))
      (node (ref "R16") (pin "1") (pinfunction "1_1") (pintype "passive"))
      (node (ref "U1") (pin "9") (pinfunction "PB6/PCINT6/TOSC1/XTAL1_9") (pintype "passive"))
      (node (ref "Y1") (pin "1") (pinfunction "1_1") (pintype "passive"))
    )
    (net (code "29") (name "/328P_16MHZ_XTAL2") (class "Default")
      (node (ref "C25") (pin "1") (pinfunction "1_1") (pintype "passive"))
      (node (ref "R16") (pin "2") (pinfunction "2_2") (pintype "passive"))
      (node (ref "U1") (pin "10") (pinfunction "PB7/PCINT14/TOSC2/XTAL2_10") (pintype "passive"))
      (node (ref "Y1") (pin "2") (pinfunction "2_2") (pintype "passive"))
    )
    (net (code "30") (name "/328P_AUTORESETn") (class "Default")
      (node (ref "C11") (pin "1") (pinfunction "1_1") (pintype "passive"))
      (node (ref "R18") (pin "1") (pinfunction "1_1") (pintype "passive"))
      (node (ref "U6") (pin "1") (pinfunction "1_1") (pintype "passive"))
    )
    (net (code "31") (name "/328P_BUF_RESETn") (class "Default")
      (node (ref "C32") (pin "2") (pinfunction "2_2") (pintype "passive"))
      (node (ref "R24") (pin "2") (pinfunction "2_2") (pintype "passive"))
      (node (ref "U6") (pin "2") (pinfunction "2_2") (pintype "passive"))
    )
    (net (code "32") (name "/328P_RESETn") (class "Default")
      (node (ref "J1") (pin "3") (pinfunction "3_3") (pintype "passive"))
      (node (ref "J5") (pin "5") (pinfunction "5_5") (pintype "passive"))
      (node (ref "JP3") (pin "1") (pinfunction "1_1") (pintype "passive"))
      (node (ref "R14") (pin "1") (pinfunction "1_1") (pintype "passive"))
      (node (ref "U1") (pin "1") (pinfunction "PC6/PCINT14~{/RESET}_1") (pintype "passive"))
      (node (ref "U6") (pin "4") (pinfunction "4_4") (pintype "passive"))
    )
    (net (code "33") (name "/AD0") (class "Default")
      (node (ref "J2") (pin "1") (pinfunction "1_1") (pintype "passive"))
      (node (ref "U1") (pin "23") (pinfunction "PC0/ADC0/PCINT8_23") (pintype "passive"))
    )
    (net (code "34") (name "/AD1") (class "Default")
      (node (ref "J2") (pin "2") (pinfunction "2_2") (pintype "passive"))
      (node (ref "U1") (pin "24") (pinfunction "PC1/ADC1/PCINT9_24") (pintype "passive"))
    )
    (net (code "35") (name "/AD2") (class "Default")
      (node (ref "J2") (pin "3") (pinfunction "3_3") (pintype "passive"))
      (node (ref "U1") (pin "25") (pinfunction "PC2/ADC2/PCINT10_25") (pintype "passive"))
    )
    (net (code "36") (name "/AD3") (class "Default")
      (node (ref "J2") (pin "4") (pinfunction "4_4") (pintype "passive"))
      (node (ref "U1") (pin "26") (pinfunction "PC3/ADC3/PCINT11_26") (pintype "passive"))
    )
    (net (code "37") (name "/AD4{slash}SDA") (class "Default")
      (node (ref "J2") (pin "5") (pinfunction "5_5") (pintype "passive"))
      (node (ref "J4") (pin "9") (pinfunction "9_9") (pintype "passive"))
      (node (ref "U1") (pin "27") (pinfunction "PC4/ADC4/PCINT12/SDA_27") (pintype "passive"))
    )
    (net (code "38") (name "/AD5{slash}SCL") (class "Default")
      (node (ref "J2") (pin "6") (pinfunction "6_6") (pintype "passive"))
      (node (ref "J4") (pin "10") (pinfunction "10_10") (pintype "passive"))
      (node (ref "U1") (pin "28") (pinfunction "PC5/ADC5/PCINT13/SCL_28") (pintype "passive"))
    )
    (net (code "39") (name "/BUTTON_RESETn") (class "Default")
      (node (ref "D6") (pin "2") (pinfunction "Anode_2") (pintype "passive"))
      (node (ref "R20") (pin "1") (pinfunction "1_1") (pintype "passive"))
      (node (ref "R24") (pin "1") (pinfunction "1_1") (pintype "passive"))
      (node (ref "SW1") (pin "1") (pinfunction "1_1") (pintype "passive"))
      (node (ref "SW1") (pin "2") (pinfunction "2_2") (pintype "passive"))
    )
    (net (code "40") (name "/CON_USB_N") (class "Default")
      (node (ref "J7") (pin "2") (pinfunction "2_2") (pintype "passive"))
      (node (ref "R6") (pin "1") (pinfunction "1_1") (pintype "passive"))
      (node (ref "Z1") (pin "2") (pinfunction "2_2") (pintype "passive"))
    )
    (net (code "41") (name "/CON_USB_P") (class "Default")
      (node (ref "J7") (pin "3") (pinfunction "3_3") (pintype "passive"))
      (node (ref "R7") (pin "1") (pinfunction "1_1") (pintype "passive"))
      (node (ref "Z2") (pin "2") (pinfunction "2_2") (pintype "passive"))
    )
    (net (code "42") (name "/IO0") (class "Default")
      (node (ref "J3") (pin "1") (pinfunction "1_1") (pintype "passive"))
      (node (ref "R10") (pin "2") (pinfunction "2_2") (pintype "passive"))
      (node (ref "U1") (pin "2") (pinfunction "PD0/PCINT16/RXD_2") (pintype "passive"))
    )
    (net (code "43") (name "/IO1") (class "Default")
      (node (ref "J3") (pin "2") (pinfunction "2_2") (pintype "passive"))
      (node (ref "R11") (pin "2") (pinfunction "2_2") (pintype "passive"))
      (node (ref "U1") (pin "3") (pinfunction "PD1/PCINT17/TXD_3") (pintype "passive"))
    )
    (net (code "44") (name "/IO2") (class "Default")
      (node (ref "J3") (pin "3") (pinfunction "3_3") (pintype "passive"))
      (node (ref "U1") (pin "4") (pinfunction "PD2/PCINT18/INT0_4") (pintype "passive"))
    )
    (net (code "45") (name "/IO3") (class "Default")
      (node (ref "J3") (pin "4") (pinfunction "4_4") (pintype "passive"))
      (node (ref "U1") (pin "5") (pinfunction "PD3/PCINT19/INT1/OC2B_5") (pintype "passive"))
    )
    (net (code "46") (name "/IO4") (class "Default")
      (node (ref "J3") (pin "5") (pinfunction "5_5") (pintype "passive"))
      (node (ref "U1") (pin "6") (pinfunction "PD4/PCINT20/T0/XCK_6") (pintype "passive"))
    )
    (net (code "47") (name "/IO5") (class "Default")
      (node (ref "J3") (pin "6") (pinfunction "6_6") (pintype "passive"))
      (node (ref "U1") (pin "11") (pinfunction "PD5/PCINT21/T1/OC0B_11") (pintype "passive"))
    )
    (net (code "48") (name "/IO6") (class "Default")
      (node (ref "J3") (pin "7") (pinfunction "7_7") (pintype "passive"))
      (node (ref "U1") (pin "12") (pinfunction "PD6/PCINT22/AIN0/OC0A_12") (pintype "passive"))
    )
    (net (code "49") (name "/IO7") (class "Default")
      (node (ref "J3") (pin "8") (pinfunction "8_8") (pintype "passive"))
      (node (ref "U1") (pin "13") (pinfunction "PD7/PCINT23/AIN1_13") (pintype "passive"))
    )
    (net (code "50") (name "/IO8") (class "Default")
      (node (ref "J4") (pin "1") (pinfunction "1_1") (pintype "passive"))
      (node (ref "R22") (pin "2") (pinfunction "2_2") (pintype "passive"))
      (node (ref "U1") (pin "14") (pinfunction "PB0/PCINT0/ICP1/CLKO_14") (pintype "passive"))
    )
    (net (code "51") (name "/IO9") (class "Default")
      (node (ref "J4") (pin "2") (pinfunction "2_2") (pintype "passive"))
      (node (ref "U1") (pin "15") (pinfunction "PB1/PCINT1/OC1A_15") (pintype "passive"))
    )
    (net (code "52") (name "/MISO") (class "Default")
      (node (ref "J4") (pin "5") (pinfunction "5_5") (pintype "passive"))
      (node (ref "J5") (pin "1") (pinfunction "1_1") (pintype "passive"))
      (node (ref "U1") (pin "18") (pinfunction "PB4/PCINT4/MISO_18") (pintype "passive"))
    )
    (net (code "53") (name "/MOSI") (class "Default")
      (node (ref "J4") (pin "4") (pinfunction "4_4") (pintype "passive"))
      (node (ref "J5") (pin "4") (pinfunction "4_4") (pintype "passive"))
      (node (ref "U1") (pin "17") (pinfunction "PB3/PCINT3/OC2A/MOSI_17") (pintype "passive"))
    )
    (net (code "54") (name "/SCK") (class "Default")
      (node (ref "J4") (pin "6") (pinfunction "6_6") (pintype "passive"))
      (node (ref "J5") (pin "3") (pinfunction "3_3") (pintype "passive"))
      (node (ref "R13") (pin "2") (pinfunction "2_2") (pintype "passive"))
      (node (ref "U4") (pin "1") (pinfunction "1_1") (pintype "passive"))
      (node (ref "U4") (pin "2") (pinfunction "2_2") (pintype "passive"))
    )
    (net (code "55") (name "/SCK_R") (class "Default")
      (node (ref "R13") (pin "1") (pinfunction "1_1") (pintype "passive"))
      (node (ref "U1") (pin "19") (pinfunction "PB5/PCINT5/SCK_19") (pintype "passive"))
    )
    (net (code "56") (name "/SS") (class "Default")
      (node (ref "J4") (pin "3") (pinfunction "3_3") (pintype "passive"))
      (node (ref "U1") (pin "16") (pinfunction "PB2/PCINT2/OSC1B~{/SS}_16") (pintype "passive"))
    )
    (net (code "57") (name "/USB_N") (class "Default")
      (node (ref "R6") (pin "2") (pinfunction "2_2") (pintype "passive"))
      (node (ref "U2") (pin "30") (pinfunction "D-_30") (pintype "passive"))
    )
    (net (code "58") (name "/USB_P") (class "Default")
      (node (ref "R7") (pin "2") (pinfunction "2_2") (pintype "passive"))
      (node (ref "U2") (pin "29") (pinfunction "D+_29") (pintype "passive"))
    )
    (net (code "59") (name "/USER_BUTTON") (class "Default")
      (node (ref "R21") (pin "1") (pinfunction "1_1") (pintype "passive"))
      (node (ref "R25") (pin "1") (pinfunction "1_1") (pintype "passive"))
      (node (ref "SW2") (pin "1") (pinfunction "1_1") (pintype "passive"))
      (node (ref "SW2") (pin "2") (pinfunction "2_2") (pintype "passive"))
    )
    (net (code "60") (name "/USER_BUTTON_BUF") (class "Default")
      (node (ref "C33") (pin "2") (pinfunction "2_2") (pintype "passive"))
      (node (ref "R25") (pin "2") (pinfunction "2_2") (pintype "passive"))
      (node (ref "U7") (pin "1") (pinfunction "1_1") (pintype "passive"))
      (node (ref "U7") (pin "2") (pinfunction "2_2") (pintype "passive"))
    )
    (net (code "61") (name "GND") (class "Default")
      (node (ref "C1") (pin "2") (pinfunction "2_2") (pintype "passive"))
      (node (ref "C10") (pin "2") (pinfunction "2_2") (pintype "passive"))
      (node (ref "C12") (pin "1") (pinfunction "1_1") (pintype "passive"))
      (node (ref "C13") (pin "1") (pinfunction "1_1") (pintype "passive"))
      (node (ref "C14") (pin "1") (pinfunction "1_1") (pintype "passive"))
      (node (ref "C15") (pin "1") (pinfunction "1_1") (pintype "passive"))
      (node (ref "C16") (pin "1") (pinfunction "1_1") (pintype "passive"))
      (node (ref "C17") (pin "1") (pinfunction "1_1") (pintype "passive"))
      (node (ref "C19") (pin "2") (pinfunction "2_2") (pintype "passive"))
      (node (ref "C2") (pin "2") (pinfunction "2_2") (pintype "passive"))
      (node (ref "C20") (pin "1") (pinfunction "1_1") (pintype "passive"))
      (node (ref "C21") (pin "1") (pinfunction "1_1") (pintype "passive"))
      (node (ref "C22") (pin "2") (pinfunction "2_2") (pintype "passive"))
      (node (ref "C23") (pin "1") (pinfunction "1_1") (pintype "passive"))
      (node (ref "C24") (pin "1") (pinfunction "1_1") (pintype "passive"))
      (node (ref "C25") (pin "2") (pinfunction "2_2") (pintype "passive"))
      (node (ref "C26") (pin "1") (pinfunction "1_1") (pintype "passive"))
      (node (ref "C27") (pin "2") (pinfunction "2_2") (pintype "passive"))
      (node (ref "C28") (pin "1") (pinfunction "1_1") (pintype "passive"))
      (node (ref "C29") (pin "1") (pinfunction "1_1") (pintype "passive"))
      (node (ref "C3") (pin "1") (pinfunction "1_1") (pintype "passive"))
      (node (ref "C30") (pin "1") (pinfunction "1_1") (pintype "passive"))
      (node (ref "C31") (pin "1") (pinfunction "1_1") (pintype "passive"))
      (node (ref "C32") (pin "1") (pinfunction "1_1") (pintype "passive"))
      (node (ref "C33") (pin "1") (pinfunction "1_1") (pintype "passive"))
      (node (ref "C34") (pin "1") (pinfunction "1_1") (pintype "passive"))
      (node (ref "C4") (pin "1") (pinfunction "1_1") (pintype "passive"))
      (node (ref "C5") (pin "1") (pinfunction "1_1") (pintype "passive"))
      (node (ref "C6") (pin "1") (pinfunction "1_1") (pintype "passive"))
      (node (ref "C7") (pin "1") (pinfunction "1_1") (pintype "passive"))
      (node (ref "C8") (pin "1") (pinfunction "1_1") (pintype "passive"))
      (node (ref "C9") (pin "2") (pinfunction "2_2") (pintype "passive"))
      (node (ref "D1") (pin "1") (pinfunction "Cathode_1") (pintype "passive"))
      (node (ref "J1") (pin "6") (pinfunction "6_6") (pintype "passive"))
      (node (ref "J1") (pin "7") (pinfunction "7_7") (pintype "passive"))
      (node (ref "J4") (pin "7") (pinfunction "7_7") (pintype "passive"))
      (node (ref "J5") (pin "6") (pinfunction "6_6") (pintype "passive"))
      (node (ref "J6") (pin "6") (pinfunction "6_6") (pintype "passive"))
      (node (ref "J7") (pin "10") (pinfunction "10_10") (pintype "passive"))
      (node (ref "J7") (pin "11") (pinfunction "11_11") (pintype "passive"))
      (node (ref "J7") (pin "5") (pinfunction "5_5") (pintype "passive"))
      (node (ref "J7") (pin "6") (pinfunction "6_6") (pintype "passive"))
      (node (ref "J7") (pin "7") (pinfunction "7_7") (pintype "passive"))
      (node (ref "J7") (pin "8") (pinfunction "8_8") (pintype "passive"))
      (node (ref "J7") (pin "9") (pinfunction "9_9") (pintype "passive"))
      (node (ref "J9") (pin "1") (pinfunction "1_1") (pintype "passive"))
      (node (ref "MH1") (pin "1") (pinfunction "1_1") (pintype "passive"))
      (node (ref "MH2") (pin "1") (pinfunction "1_1") (pintype "passive"))
      (node (ref "MH3") (pin "1") (pinfunction "1_1") (pintype "passive"))
      (node (ref "R12") (pin "1") (pinfunction "1_1") (pintype "passive"))
      (node (ref "R8") (pin "2") (pinfunction "2_2") (pintype "passive"))
      (node (ref "SW1") (pin "3") (pinfunction "3_3") (pintype "passive"))
      (node (ref "SW1") (pin "4") (pinfunction "4_4") (pintype "passive"))
      (node (ref "SW2") (pin "3") (pinfunction "3_3") (pintype "passive"))
      (node (ref "SW2") (pin "4") (pinfunction "4_4") (pintype "passive"))
      (node (ref "U1") (pin "22") (pinfunction "GND_2_22") (pintype "passive"))
      (node (ref "U1") (pin "8") (pinfunction "GND_1_8") (pintype "passive"))
      (node (ref "U2") (pin "28") (pinfunction "UGND_28") (pintype "passive"))
      (node (ref "U2") (pin "3") (pinfunction "GND_3") (pintype "passive"))
      (node (ref "U3") (pin "3") (pinfunction "GND_3") (pintype "passive"))
      (node (ref "U3") (pin "6") (pinfunction "EPAD_6") (pintype "passive"))
      (node (ref "U4") (pin "3") (pinfunction "3_3") (pintype "passive"))
      (node (ref "U5") (pin "3") (pinfunction "3_3") (pintype "passive"))
      (node (ref "U6") (pin "3") (pinfunction "3_3") (pintype "passive"))
      (node (ref "U7") (pin "3") (pinfunction "3_3") (pintype "passive"))
      (node (ref "Z1") (pin "1") (pinfunction "1_1") (pintype "passive"))
      (node (ref "Z2") (pin "1") (pinfunction "1_1") (pintype "passive"))
    )
    (net (code "62") (name "Net-(C11-Pad2)") (class "Default")
      (node (ref "C11") (pin "2") (pinfunction "2_2") (pintype "passive"))
      (node (ref "JP1") (pin "1") (pinfunction "1_1") (pintype "passive"))
    )
    (net (code "63") (name "Net-(D1-Anode)") (class "Default")
      (node (ref "D1") (pin "2") (pinfunction "Anode_2") (pintype "passive"))
      (node (ref "R17") (pin "1") (pinfunction "1_1") (pintype "passive"))
    )
    (net (code "64") (name "Net-(D2-Anode)") (class "Default")
      (node (ref "D2") (pin "2") (pinfunction "Anode_2") (pintype "passive"))
      (node (ref "R15") (pin "1") (pinfunction "1_1") (pintype "passive"))
    )
    (net (code "65") (name "Net-(D2-Cathode)") (class "Default")
      (node (ref "D2") (pin "1") (pinfunction "Cathode_1") (pintype "passive"))
      (node (ref "U4") (pin "4") (pinfunction "4_4") (pintype "passive"))
    )
    (net (code "66") (name "Net-(D3-Anode)") (class "Default")
      (node (ref "D3") (pin "2") (pinfunction "Anode_2") (pintype "passive"))
      (node (ref "R2") (pin "1") (pinfunction "1_1") (pintype "passive"))
    )
    (net (code "67") (name "Net-(D4-Anode)") (class "Default")
      (node (ref "D4") (pin "2") (pinfunction "Anode_2") (pintype "passive"))
      (node (ref "R3") (pin "1") (pinfunction "1_1") (pintype "passive"))
    )
    (net (code "68") (name "Net-(D5-Anode)") (class "Default")
      (node (ref "D5") (pin "2") (pinfunction "Anode_2") (pintype "passive"))
      (node (ref "R19") (pin "1") (pinfunction "1_1") (pintype "passive"))
      (node (ref "R23") (pin "1") (pinfunction "1_1") (pintype "passive"))
    )
    (net (code "69") (name "Net-(J7-Pad4)") (class "Default")
      (node (ref "J7") (pin "4") (pinfunction "4_4") (pintype "passive"))
      (node (ref "R8") (pin "1") (pinfunction "1_1") (pintype "passive"))
    )
    (net (code "70") (name "Net-(JP1-Pad3)") (class "Default")
      (node (ref "JP1") (pin "3") (pinfunction "3_3") (pintype "passive"))
      (node (ref "R12") (pin "2") (pinfunction "2_2") (pintype "passive"))
    )
    (net (code "71") (name "Net-(R22-Pad1)") (class "Default")
      (node (ref "R22") (pin "1") (pinfunction "1_1") (pintype "passive"))
      (node (ref "U7") (pin "4") (pinfunction "4_4") (pintype "passive"))
    )
    (net (code "72") (name "unconnected-(J1-Pad1)") (class "Default")
      (node (ref "J1") (pin "1") (pinfunction "1_1") (pintype "passive+no_connect"))
    )
    (net (code "73") (name "unconnected-(J1-Pad8)") (class "Default")
      (node (ref "J1") (pin "8") (pinfunction "8_8") (pintype "passive+no_connect"))
    )
    (net (code "74") (name "unconnected-(MH4-Pad1)") (class "Default")
      (node (ref "MH4") (pin "1") (pinfunction "1_1") (pintype "passive+no_connect"))
    )
    (net (code "75") (name "unconnected-(U2-AIN0{slash}INT1{slash}PD1-Pad7)") (class "Default")
      (node (ref "U2") (pin "7") (pinfunction "AIN0/INT1/PD1_7") (pintype "passive+no_connect"))
    )
    (net (code "76") (name "unconnected-(U2-AIN2{slash}PCINT11{slash}PC2-Pad5)") (class "Default")
      (node (ref "U2") (pin "5") (pinfunction "AIN2/PCINT11/PC2_5") (pintype "passive+no_connect"))
    )
    (net (code "77") (name "unconnected-(U2-CLKO{slash}ICP1{slash}INT4{slash}PC7-Pad22)") (class "Default")
      (node (ref "U2") (pin "22") (pinfunction "CLKO/ICP1/INT4/PC7_22") (pintype "passive+no_connect"))
    )
    (net (code "78") (name "unconnected-(U2-OC.0B{slash}INT0{slash}PD0-Pad6)") (class "Default")
      (node (ref "U2") (pin "6") (pinfunction "OC.0B/INT0/PD0_6") (pintype "passive+no_connect"))
    )
    (net (code "79") (name "unconnected-(U2-OC.1A{slash}PCINT8{slash}PC6-Pad23)") (class "Default")
      (node (ref "U2") (pin "23") (pinfunction "OC.1A/PCINT8/PC6_23") (pintype "passive+no_connect"))
    )
    (net (code "80") (name "unconnected-(U2-OC.1B{slash}PCINT9{slash}PC5-Pad25)") (class "Default")
      (node (ref "U2") (pin "25") (pinfunction "OC.1B/PCINT9/PC5_25") (pintype "passive+no_connect"))
    )
    (net (code "81") (name "unconnected-(U2-PCINT10{slash}PC4-Pad26)") (class "Default")
      (node (ref "U2") (pin "26") (pinfunction "PCINT10/PC4_26") (pintype "passive+no_connect"))
    )
    (net (code "82") (name "unconnected-(U2-~{RTS}{slash}AIN5{slash}INT6{slash}PD6-Pad12)") (class "Default")
      (node (ref "U2") (pin "12") (pinfunction "~{RTS}/AIN5/INT6/PD6_12") (pintype "passive+no_connect"))
    )
    (net (code "83") (name "unconnected-(U2-~{SS}{slash}PCINT0{slash}PB0-Pad14)") (class "Default")
      (node (ref "U2") (pin "14") (pinfunction "~{SS}/PCINT0/PB0_14") (pintype "passive+no_connect"))
    )
  )
)
